# l5973d_mod.net
KiCad netlist of a schematic drawn in EAGLE
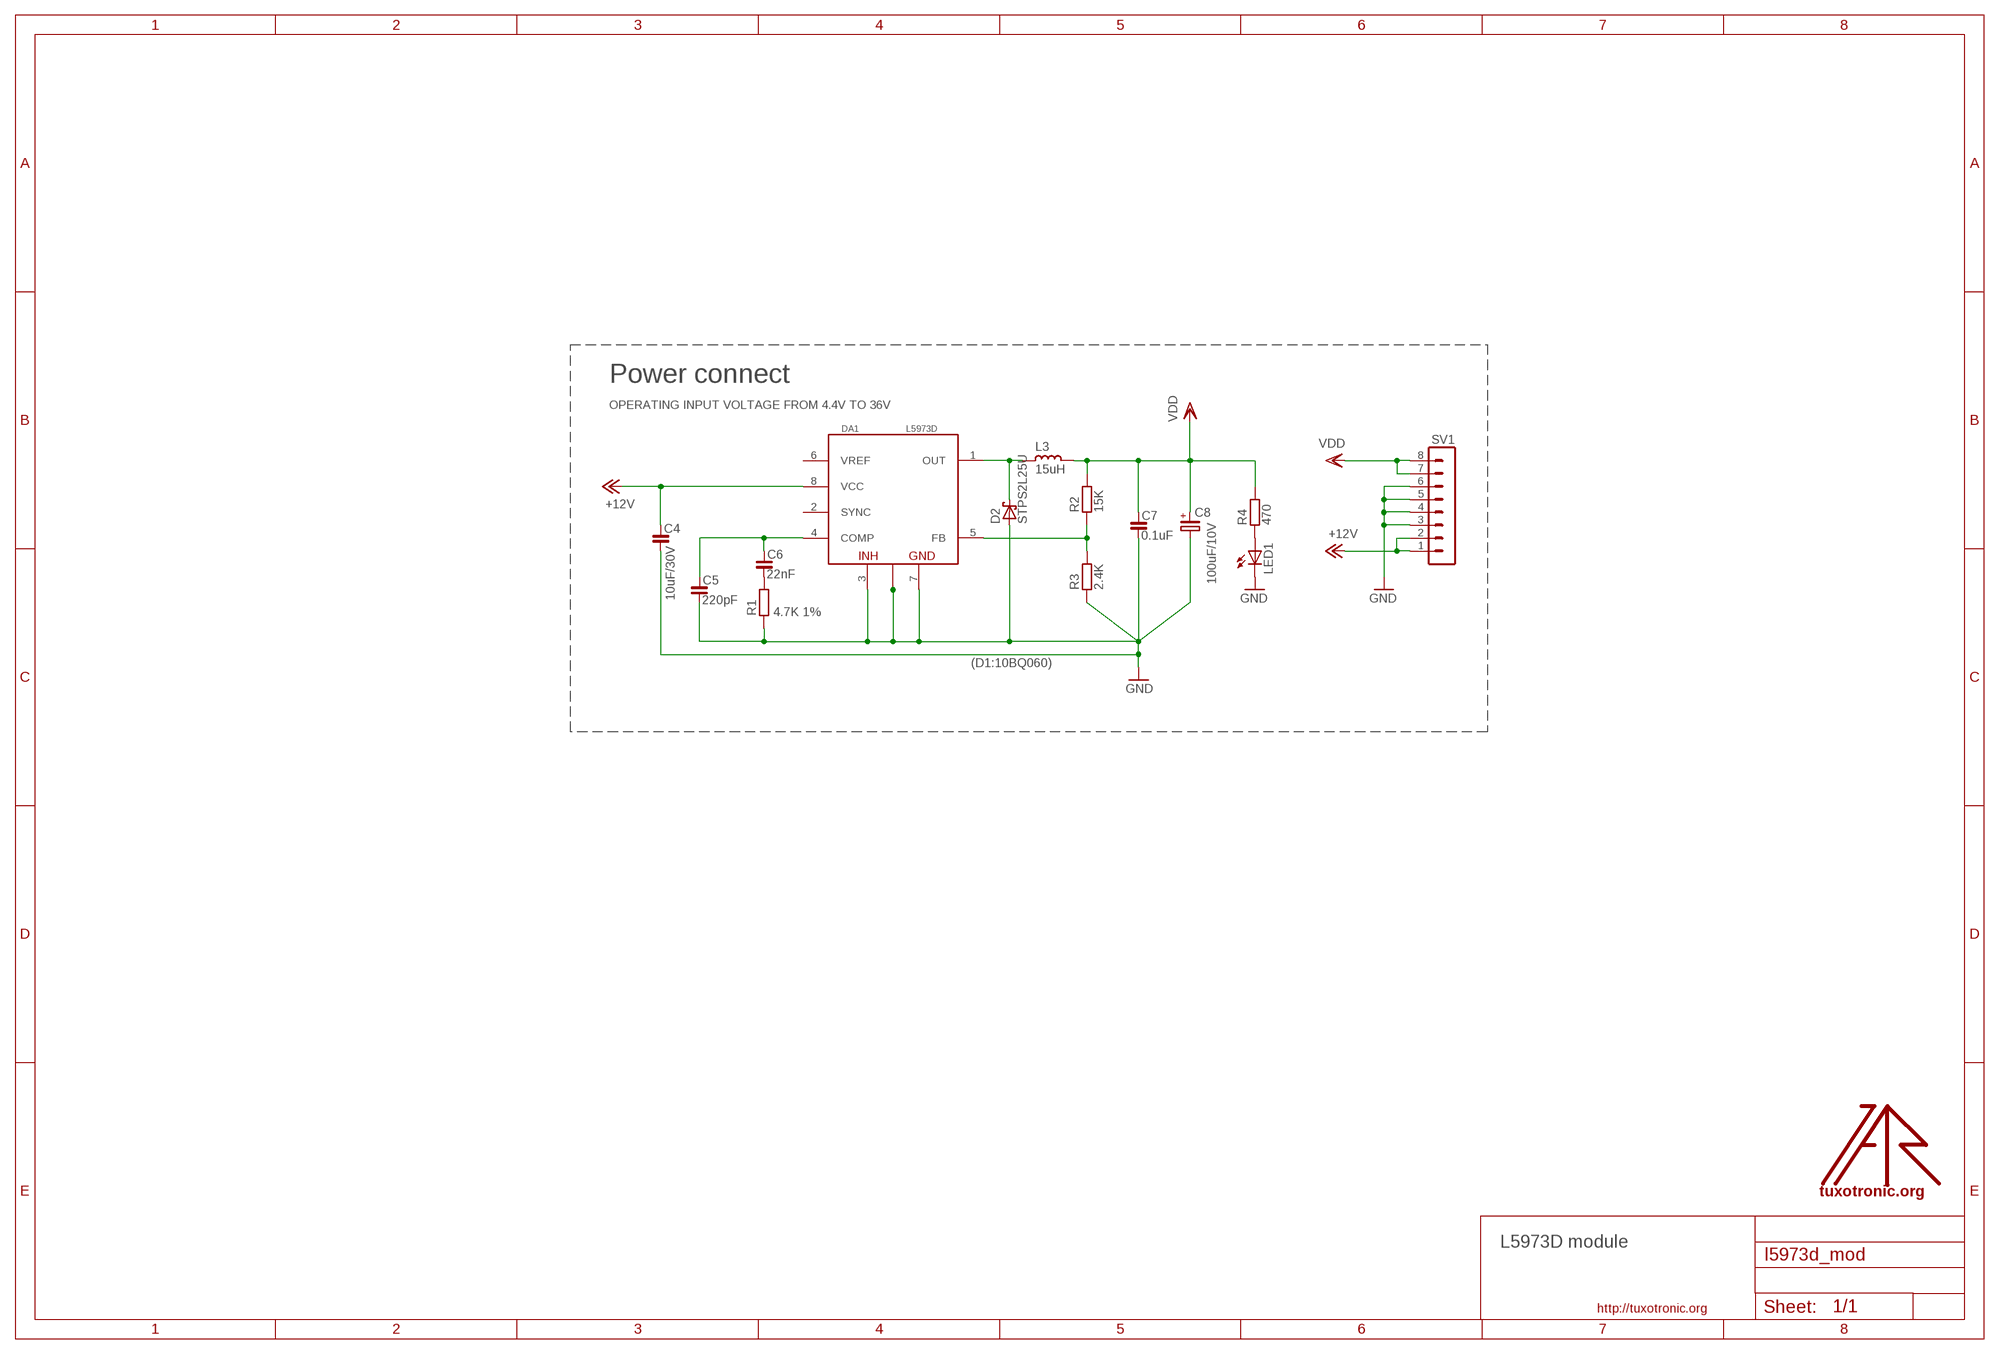
[diagram p0: schematic, sheet 1]

(export (version "E")
  (design (tool "Eeschema 10.0.6"))
  (components
    (comp (ref "C4")
      (value "10uF/30V")
      (footprint "eagle-import:C1210")
      (libsource (lib "eagle-import") (part "C_1210"))
    )
    (comp (ref "C5")
      (value "220pF")
      (footprint "eagle-import:C0603")
      (libsource (lib "eagle-import") (part "C_0603"))
    )
    (comp (ref "C6")
      (value "22nF")
      (footprint "eagle-import:C0603")
      (libsource (lib "eagle-import") (part "C_0603"))
    )
    (comp (ref "C7")
      (value "0.1uF")
      (footprint "eagle-import:C0805")
      (libsource (lib "eagle-import") (part "C_0805"))
    )
    (comp (ref "C8")
      (value "100uF/10V")
      (footprint "eagle-import:CE-035X080")
      (libsource (lib "eagle-import") (part "CP_E-035X080"))
    )
    (comp (ref "D2")
      (value "STPS2L25U")
      (footprint "eagle-import:SMB")
      (libsource (lib "eagle-import") (part "SCHOTTKY-DIODESMD"))
    )
    (comp (ref "DA1")
      (value "L5973D")
      (footprint "eagle-import:HSOP8-PAD")
      (libsource (lib "eagle-import") (part "L5973D"))
    )
    (comp (ref "L3")
      (value "15uH")
      (footprint "eagle-import:CD75")
      (libsource (lib "eagle-import") (part "L_CD75"))
    )
    (comp (ref "LED1")
      (value "LEDCHIPLED_0805")
      (footprint "eagle-import:CHIPLED_0805")
      (libsource (lib "eagle-import") (part "LEDCHIPLED_0805"))
    )
    (comp (ref "R1")
      (value "4.7K 1%")
      (footprint "eagle-import:R0603")
      (libsource (lib "eagle-import") (part "R_0603"))
    )
    (comp (ref "R2")
      (value "15K")
      (footprint "eagle-import:R0603")
      (libsource (lib "eagle-import") (part "R_0603"))
    )
    (comp (ref "R3")
      (value "2.4K")
      (footprint "eagle-import:R0603")
      (libsource (lib "eagle-import") (part "R_0603"))
    )
    (comp (ref "R4")
      (value "470")
      (footprint "eagle-import:R0603")
      (libsource (lib "eagle-import") (part "R_0603"))
    )
    (comp (ref "SV1")
      (value "MA08-1W")
      (footprint "eagle-import:MA08-1W")
      (libsource (lib "eagle-import") (part "MA08-1W"))
    )
    (comp (ref "U$1")
      (value "LOGO")
      (footprint "eagle-import:TT_LOGO")
      (libsource (lib "eagle-import") (part "LOGO"))
    )
  )
  (nets
    (net (code "1") (name "+12V") (class "Default")
      (node (ref "C4") (pin "1") (pinfunction "1_1") (pintype "passive"))
      (node (ref "DA1") (pin "8") (pinfunction "VCC_8") (pintype "power_in"))
      (node (ref "SV1") (pin "1") (pinfunction "1_1") (pintype "passive"))
      (node (ref "SV1") (pin "2") (pinfunction "2_2") (pintype "passive"))
    )
    (net (code "2") (name "GND") (class "Default")
      (node (ref "C4") (pin "2") (pinfunction "2_2") (pintype "passive"))
      (node (ref "C5") (pin "2") (pinfunction "2_2") (pintype "passive"))
      (node (ref "C7") (pin "2") (pinfunction "2_2") (pintype "passive"))
      (node (ref "C8") (pin "-") (pinfunction "-_-") (pintype "passive"))
      (node (ref "D2") (pin "A") (pinfunction "A_A") (pintype "passive"))
      (node (ref "DA1") (pin "3") (pinfunction "INH_3") (pintype "input"))
      (node (ref "DA1") (pin "7") (pinfunction "GND_7") (pintype "power_in"))
      (node (ref "DA1") (pin "P") (pinfunction "GND_P") (pintype "power_in"))
      (node (ref "LED1") (pin "C") (pinfunction "C_C") (pintype "passive"))
      (node (ref "R1") (pin "1") (pinfunction "1_1") (pintype "passive"))
      (node (ref "R3") (pin "1") (pinfunction "1_1") (pintype "passive"))
      (node (ref "SV1") (pin "3") (pinfunction "3_3") (pintype "passive"))
      (node (ref "SV1") (pin "4") (pinfunction "4_4") (pintype "passive"))
      (node (ref "SV1") (pin "5") (pinfunction "5_5") (pintype "passive"))
      (node (ref "SV1") (pin "6") (pinfunction "6_6") (pintype "passive"))
    )
    (net (code "3") (name "Net-(C6-Pad2)") (class "Default")
      (node (ref "C6") (pin "2") (pinfunction "2_2") (pintype "passive"))
      (node (ref "R1") (pin "2") (pinfunction "2_2") (pintype "passive"))
    )
    (net (code "4") (name "Net-(DA1-COMP)") (class "Default")
      (node (ref "C5") (pin "1") (pinfunction "1_1") (pintype "passive"))
      (node (ref "C6") (pin "1") (pinfunction "1_1") (pintype "passive"))
      (node (ref "DA1") (pin "4") (pinfunction "COMP_4") (pintype "bidirectional"))
    )
    (net (code "5") (name "Net-(DA1-FB)") (class "Default")
      (node (ref "DA1") (pin "5") (pinfunction "FB_5") (pintype "input"))
      (node (ref "R2") (pin "1") (pinfunction "1_1") (pintype "passive"))
      (node (ref "R3") (pin "2") (pinfunction "2_2") (pintype "passive"))
    )
    (net (code "6") (name "Net-(DA1-OUT)") (class "Default")
      (node (ref "D2") (pin "C") (pinfunction "C_C") (pintype "passive"))
      (node (ref "DA1") (pin "1") (pinfunction "OUT_1") (pintype "output"))
      (node (ref "L3") (pin "2") (pinfunction "2_2") (pintype "passive"))
    )
    (net (code "7") (name "Net-(LED1-PadA)") (class "Default")
      (node (ref "LED1") (pin "A") (pinfunction "A_A") (pintype "passive"))
      (node (ref "R4") (pin "1") (pinfunction "1_1") (pintype "passive"))
    )
    (net (code "8") (name "VDD") (class "Default")
      (node (ref "C7") (pin "1") (pinfunction "1_1") (pintype "passive"))
      (node (ref "C8") (pin "+") (pinfunction "+_+") (pintype "passive"))
      (node (ref "L3") (pin "1") (pinfunction "1_1") (pintype "passive"))
      (node (ref "R2") (pin "2") (pinfunction "2_2") (pintype "passive"))
      (node (ref "R4") (pin "2") (pinfunction "2_2") (pintype "passive"))
      (node (ref "SV1") (pin "7") (pinfunction "7_7") (pintype "passive"))
      (node (ref "SV1") (pin "8") (pinfunction "8_8") (pintype "passive"))
    )
    (net (code "9") (name "unconnected-(DA1-SYNC-Pad2)") (class "Default")
      (node (ref "DA1") (pin "2") (pinfunction "SYNC_2") (pintype "passive"))
    )
    (net (code "10") (name "unconnected-(DA1-VREF-Pad6)") (class "Default")
      (node (ref "DA1") (pin "6") (pinfunction "VREF_6") (pintype "output"))
    )
  )
)
